# pov-globe2.net
KiCad netlist of a schematic drawn in EAGLE
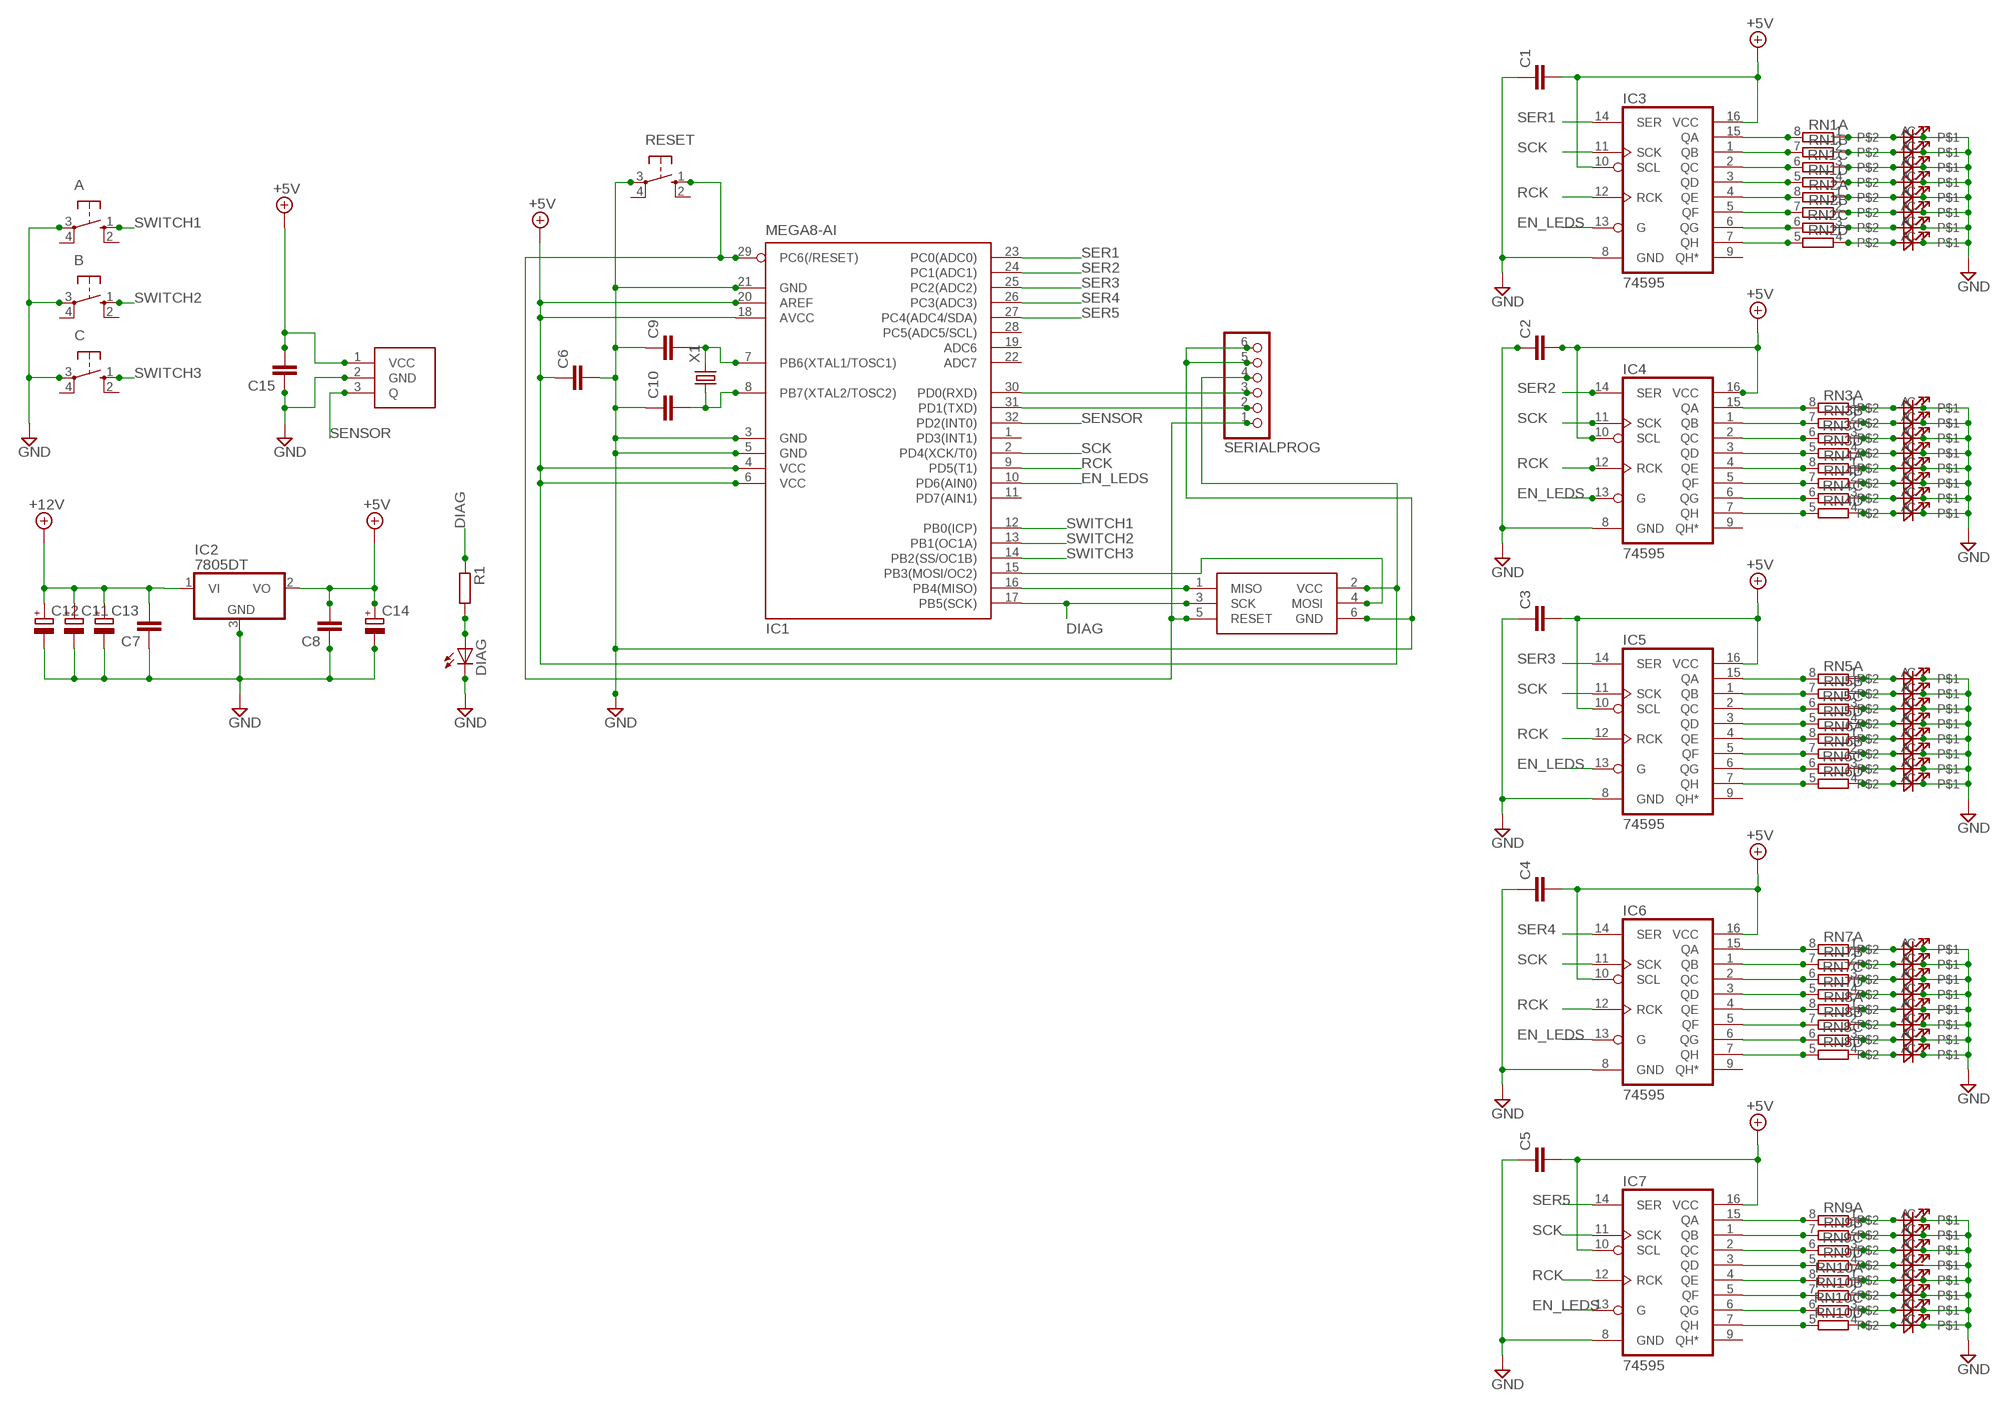
[diagram p0: schematic, sheet 1]

(export (version "E")
  (design (tool "Eeschema 10.0.6"))
  (components
    (comp (ref "0")
      (value "3MMLEDSIDELED1_8MMSIDE")
      (footprint "eagle-import:LED1_8MMSIDE")
      (libsource (lib "eagle-import") (part "3MMLEDSIDELED1_8MMSIDE"))
    )
    (comp (ref "1")
      (value "3MMLEDSIDELED1_8MMSIDE")
      (footprint "eagle-import:LED1_8MMSIDE")
      (libsource (lib "eagle-import") (part "3MMLEDSIDELED1_8MMSIDE"))
    )
    (comp (ref "2")
      (value "3MMLEDSIDELED1_8MMSIDE")
      (footprint "eagle-import:LED1_8MMSIDE")
      (libsource (lib "eagle-import") (part "3MMLEDSIDELED1_8MMSIDE"))
    )
    (comp (ref "3")
      (value "3MMLEDSIDELED1_8MMSIDE")
      (footprint "eagle-import:LED1_8MMSIDE")
      (libsource (lib "eagle-import") (part "3MMLEDSIDELED1_8MMSIDE"))
    )
    (comp (ref "4")
      (value "3MMLEDSIDELED1_8MMSIDE")
      (footprint "eagle-import:LED1_8MMSIDE")
      (libsource (lib "eagle-import") (part "3MMLEDSIDELED1_8MMSIDE"))
    )
    (comp (ref "5")
      (value "3MMLEDSIDELED1_8MMSIDE")
      (footprint "eagle-import:LED1_8MMSIDE")
      (libsource (lib "eagle-import") (part "3MMLEDSIDELED1_8MMSIDE"))
    )
    (comp (ref "6")
      (value "3MMLEDSIDELED1_8MMSIDE")
      (footprint "eagle-import:LED1_8MMSIDE")
      (libsource (lib "eagle-import") (part "3MMLEDSIDELED1_8MMSIDE"))
    )
    (comp (ref "7")
      (value "3MMLEDSIDELED1_8MMSIDE")
      (footprint "eagle-import:LED1_8MMSIDE")
      (libsource (lib "eagle-import") (part "3MMLEDSIDELED1_8MMSIDE"))
    )
    (comp (ref "8")
      (value "3MMLEDSIDELED1_8MMSIDE")
      (footprint "eagle-import:LED1_8MMSIDE")
      (libsource (lib "eagle-import") (part "3MMLEDSIDELED1_8MMSIDE"))
    )
    (comp (ref "9")
      (value "3MMLEDSIDELED1_8MMSIDE")
      (footprint "eagle-import:LED1_8MMSIDE")
      (libsource (lib "eagle-import") (part "3MMLEDSIDELED1_8MMSIDE"))
    )
    (comp (ref "10")
      (value "3MMLEDSIDELED1_8MMSIDE")
      (footprint "eagle-import:LED1_8MMSIDE")
      (libsource (lib "eagle-import") (part "3MMLEDSIDELED1_8MMSIDE"))
    )
    (comp (ref "11")
      (value "3MMLEDSIDELED1_8MMSIDE")
      (footprint "eagle-import:LED1_8MMSIDE")
      (libsource (lib "eagle-import") (part "3MMLEDSIDELED1_8MMSIDE"))
    )
    (comp (ref "12")
      (value "3MMLEDSIDELED1_8MMSIDE")
      (footprint "eagle-import:LED1_8MMSIDE")
      (libsource (lib "eagle-import") (part "3MMLEDSIDELED1_8MMSIDE"))
    )
    (comp (ref "13")
      (value "3MMLEDSIDELED1_8MMSIDE")
      (footprint "eagle-import:LED1_8MMSIDE")
      (libsource (lib "eagle-import") (part "3MMLEDSIDELED1_8MMSIDE"))
    )
    (comp (ref "14")
      (value "3MMLEDSIDELED1_8MMSIDE")
      (footprint "eagle-import:LED1_8MMSIDE")
      (libsource (lib "eagle-import") (part "3MMLEDSIDELED1_8MMSIDE"))
    )
    (comp (ref "15")
      (value "3MMLEDSIDELED1_8MMSIDE")
      (footprint "eagle-import:LED1_8MMSIDE")
      (libsource (lib "eagle-import") (part "3MMLEDSIDELED1_8MMSIDE"))
    )
    (comp (ref "16")
      (value "3MMLEDSIDELED1_8MMSIDE")
      (footprint "eagle-import:LED1_8MMSIDE")
      (libsource (lib "eagle-import") (part "3MMLEDSIDELED1_8MMSIDE"))
    )
    (comp (ref "17")
      (value "3MMLEDSIDELED1_8MMSIDE")
      (footprint "eagle-import:LED1_8MMSIDE")
      (libsource (lib "eagle-import") (part "3MMLEDSIDELED1_8MMSIDE"))
    )
    (comp (ref "18")
      (value "3MMLEDSIDELED1_8MMSIDE")
      (footprint "eagle-import:LED1_8MMSIDE")
      (libsource (lib "eagle-import") (part "3MMLEDSIDELED1_8MMSIDE"))
    )
    (comp (ref "19")
      (value "3MMLEDSIDELED1_8MMSIDE")
      (footprint "eagle-import:LED1_8MMSIDE")
      (libsource (lib "eagle-import") (part "3MMLEDSIDELED1_8MMSIDE"))
    )
    (comp (ref "20")
      (value "3MMLEDSIDELED1_8MMSIDE")
      (footprint "eagle-import:LED1_8MMSIDE")
      (libsource (lib "eagle-import") (part "3MMLEDSIDELED1_8MMSIDE"))
    )
    (comp (ref "21")
      (value "3MMLEDSIDELED1_8MMSIDE")
      (footprint "eagle-import:LED1_8MMSIDE")
      (libsource (lib "eagle-import") (part "3MMLEDSIDELED1_8MMSIDE"))
    )
    (comp (ref "22")
      (value "3MMLEDSIDELED1_8MMSIDE")
      (footprint "eagle-import:LED1_8MMSIDE")
      (libsource (lib "eagle-import") (part "3MMLEDSIDELED1_8MMSIDE"))
    )
    (comp (ref "23")
      (value "3MMLEDSIDELED1_8MMSIDE")
      (footprint "eagle-import:LED1_8MMSIDE")
      (libsource (lib "eagle-import") (part "3MMLEDSIDELED1_8MMSIDE"))
    )
    (comp (ref "24")
      (value "3MMLEDSIDELED1_8MMSIDE")
      (footprint "eagle-import:LED1_8MMSIDE")
      (libsource (lib "eagle-import") (part "3MMLEDSIDELED1_8MMSIDE"))
    )
    (comp (ref "25")
      (value "3MMLEDSIDELED1_8MMSIDE")
      (footprint "eagle-import:LED1_8MMSIDE")
      (libsource (lib "eagle-import") (part "3MMLEDSIDELED1_8MMSIDE"))
    )
    (comp (ref "26")
      (value "3MMLEDSIDELED1_8MMSIDE")
      (footprint "eagle-import:LED1_8MMSIDE")
      (libsource (lib "eagle-import") (part "3MMLEDSIDELED1_8MMSIDE"))
    )
    (comp (ref "27")
      (value "3MMLEDSIDELED1_8MMSIDE")
      (footprint "eagle-import:LED1_8MMSIDE")
      (libsource (lib "eagle-import") (part "3MMLEDSIDELED1_8MMSIDE"))
    )
    (comp (ref "28")
      (value "3MMLEDSIDELED1_8MMSIDE")
      (footprint "eagle-import:LED1_8MMSIDE")
      (libsource (lib "eagle-import") (part "3MMLEDSIDELED1_8MMSIDE"))
    )
    (comp (ref "29")
      (value "3MMLEDSIDELED1_8MMSIDE")
      (footprint "eagle-import:LED1_8MMSIDE")
      (libsource (lib "eagle-import") (part "3MMLEDSIDELED1_8MMSIDE"))
    )
    (comp (ref "30")
      (value "3MMLEDSIDELED1_8MMSIDE")
      (footprint "eagle-import:LED1_8MMSIDE")
      (libsource (lib "eagle-import") (part "3MMLEDSIDELED1_8MMSIDE"))
    )
    (comp (ref "31")
      (value "3MMLEDSIDELED1_8MMSIDE")
      (footprint "eagle-import:LED1_8MMSIDE")
      (libsource (lib "eagle-import") (part "3MMLEDSIDELED1_8MMSIDE"))
    )
    (comp (ref "32")
      (value "3MMLEDSIDELED1_8MMSIDE")
      (footprint "eagle-import:LED1_8MMSIDE")
      (libsource (lib "eagle-import") (part "3MMLEDSIDELED1_8MMSIDE"))
    )
    (comp (ref "33")
      (value "3MMLEDSIDELED1_8MMSIDE")
      (footprint "eagle-import:LED1_8MMSIDE")
      (libsource (lib "eagle-import") (part "3MMLEDSIDELED1_8MMSIDE"))
    )
    (comp (ref "34")
      (value "3MMLEDSIDELED1_8MMSIDE")
      (footprint "eagle-import:LED1_8MMSIDE")
      (libsource (lib "eagle-import") (part "3MMLEDSIDELED1_8MMSIDE"))
    )
    (comp (ref "35")
      (value "3MMLEDSIDELED1_8MMSIDE")
      (footprint "eagle-import:LED1_8MMSIDE")
      (libsource (lib "eagle-import") (part "3MMLEDSIDELED1_8MMSIDE"))
    )
    (comp (ref "36")
      (value "3MMLEDSIDELED1_8MMSIDE")
      (footprint "eagle-import:LED1_8MMSIDE")
      (libsource (lib "eagle-import") (part "3MMLEDSIDELED1_8MMSIDE"))
    )
    (comp (ref "37")
      (value "3MMLEDSIDELED1_8MMSIDE")
      (footprint "eagle-import:LED1_8MMSIDE")
      (libsource (lib "eagle-import") (part "3MMLEDSIDELED1_8MMSIDE"))
    )
    (comp (ref "38")
      (value "3MMLEDSIDELED1_8MMSIDE")
      (footprint "eagle-import:LED1_8MMSIDE")
      (libsource (lib "eagle-import") (part "3MMLEDSIDELED1_8MMSIDE"))
    )
    (comp (ref "39")
      (value "3MMLEDSIDELED1_8MMSIDE")
      (footprint "eagle-import:LED1_8MMSIDE")
      (libsource (lib "eagle-import") (part "3MMLEDSIDELED1_8MMSIDE"))
    )
    (comp (ref "A")
      (value "10-XX")
      (footprint "eagle-import:B3F-10XX")
      (libsource (lib "eagle-import") (part "10-XX"))
    )
    (comp (ref "B")
      (value "10-XX")
      (footprint "eagle-import:B3F-10XX")
      (libsource (lib "eagle-import") (part "10-XX"))
    )
    (comp (ref "C")
      (value "10-XX")
      (footprint "eagle-import:B3F-10XX")
      (libsource (lib "eagle-import") (part "10-XX"))
    )
    (comp (ref "C1")
      (value "C-EUC0805")
      (footprint "eagle-import:C0805")
      (libsource (lib "eagle-import") (part "C-EUC0805"))
    )
    (comp (ref "C2")
      (value "C-EUC0805")
      (footprint "eagle-import:C0805")
      (libsource (lib "eagle-import") (part "C-EUC0805"))
    )
    (comp (ref "C3")
      (value "C-EUC0805")
      (footprint "eagle-import:C0805")
      (libsource (lib "eagle-import") (part "C-EUC0805"))
    )
    (comp (ref "C4")
      (value "C-EUC0805")
      (footprint "eagle-import:C0805")
      (libsource (lib "eagle-import") (part "C-EUC0805"))
    )
    (comp (ref "C5")
      (value "C-EUC0805")
      (footprint "eagle-import:C0805")
      (libsource (lib "eagle-import") (part "C-EUC0805"))
    )
    (comp (ref "C6")
      (value "C-EUC0805")
      (footprint "eagle-import:C0805")
      (libsource (lib "eagle-import") (part "C-EUC0805"))
    )
    (comp (ref "C7")
      (value "C-EUC0805")
      (footprint "eagle-import:C0805")
      (libsource (lib "eagle-import") (part "C-EUC0805"))
    )
    (comp (ref "C8")
      (value "C-EUC0805")
      (footprint "eagle-import:C0805")
      (libsource (lib "eagle-import") (part "C-EUC0805"))
    )
    (comp (ref "C9")
      (value "C-EUC0805")
      (footprint "eagle-import:C0805")
      (libsource (lib "eagle-import") (part "C-EUC0805"))
    )
    (comp (ref "C10")
      (value "C-EUC0805")
      (footprint "eagle-import:C0805")
      (libsource (lib "eagle-import") (part "C-EUC0805"))
    )
    (comp (ref "C11")
      (value "CPOL-EUE2-5")
      (footprint "eagle-import:E2-5")
      (libsource (lib "eagle-import") (part "CPOL-EUE2-5"))
    )
    (comp (ref "C12")
      (value "CPOL-EUE2-5")
      (footprint "eagle-import:E2-5")
      (libsource (lib "eagle-import") (part "CPOL-EUE2-5"))
    )
    (comp (ref "C13")
      (value "CPOL-EUE2-5")
      (footprint "eagle-import:E2-5")
      (libsource (lib "eagle-import") (part "CPOL-EUE2-5"))
    )
    (comp (ref "C14")
      (value "CPOL-EUE2-5")
      (footprint "eagle-import:E2-5")
      (libsource (lib "eagle-import") (part "CPOL-EUE2-5"))
    )
    (comp (ref "C15")
      (value "C-EUC0805")
      (footprint "eagle-import:C0805")
      (libsource (lib "eagle-import") (part "C-EUC0805"))
    )
    (comp (ref "DIAG")
      (value "LEDCHIP-LED0805")
      (footprint "eagle-import:CHIP-LED0805")
      (libsource (lib "eagle-import") (part "LEDCHIP-LED0805"))
    )
    (comp (ref "IC1")
      (value "MEGA8-AI")
      (footprint "eagle-import:TQFP32-08")
      (libsource (lib "eagle-import") (part "MEGA8-AI"))
    )
    (comp (ref "IC2")
      (value "7805DT")
      (footprint "eagle-import:TO252")
      (libsource (lib "eagle-import") (part "78DT05"))
    )
    (comp (ref "IC3")
      (value "74595")
      (footprint "eagle-import:TSSOP16")
      (libsource (lib "eagle-import") (part "74595"))
    )
    (comp (ref "IC4")
      (value "74595")
      (footprint "eagle-import:TSSOP16")
      (libsource (lib "eagle-import") (part "74595"))
    )
    (comp (ref "IC5")
      (value "74595")
      (footprint "eagle-import:TSSOP16")
      (libsource (lib "eagle-import") (part "74595"))
    )
    (comp (ref "IC6")
      (value "74595")
      (footprint "eagle-import:TSSOP16")
      (libsource (lib "eagle-import") (part "74595"))
    )
    (comp (ref "IC7")
      (value "74595")
      (footprint "eagle-import:TSSOP16")
      (libsource (lib "eagle-import") (part "74595"))
    )
    (comp (ref "ICSP")
      (value "TAG_CONN_AVR")
      (footprint "eagle-import:TC2030-MCP-NL")
      (libsource (lib "eagle-import") (part "TAG_CONN_AVR"))
    )
    (comp (ref "R1")
      (value "R-EU_R0805")
      (footprint "eagle-import:R0805")
      (libsource (lib "eagle-import") (part "R-EU_R0805"))
    )
    (comp (ref "RESET")
      (value "10-XX")
      (footprint "eagle-import:B3F-10XX")
      (libsource (lib "eagle-import") (part "10-XX"))
    )
    (comp (ref "RN1")
      (value "4R-N0603-ARC")
      (footprint "eagle-import:0603-ARC")
      (libsource (lib "eagle-import") (part "4R-N0603-ARC"))
    )
    (comp (ref "RN2")
      (value "4R-N0603-ARC")
      (footprint "eagle-import:0603-ARC")
      (libsource (lib "eagle-import") (part "4R-N0603-ARC"))
    )
    (comp (ref "RN3")
      (value "4R-N0603-ARC")
      (footprint "eagle-import:0603-ARC")
      (libsource (lib "eagle-import") (part "4R-N0603-ARC"))
    )
    (comp (ref "RN4")
      (value "4R-N0603-ARC")
      (footprint "eagle-import:0603-ARC")
      (libsource (lib "eagle-import") (part "4R-N0603-ARC"))
    )
    (comp (ref "RN5")
      (value "4R-N0603-ARC")
      (footprint "eagle-import:0603-ARC")
      (libsource (lib "eagle-import") (part "4R-N0603-ARC"))
    )
    (comp (ref "RN6")
      (value "4R-N0603-ARC")
      (footprint "eagle-import:0603-ARC")
      (libsource (lib "eagle-import") (part "4R-N0603-ARC"))
    )
    (comp (ref "RN7")
      (value "4R-N0603-ARC")
      (footprint "eagle-import:0603-ARC")
      (libsource (lib "eagle-import") (part "4R-N0603-ARC"))
    )
    (comp (ref "RN8")
      (value "4R-N0603-ARC")
      (footprint "eagle-import:0603-ARC")
      (libsource (lib "eagle-import") (part "4R-N0603-ARC"))
    )
    (comp (ref "RN9")
      (value "4R-N0603-ARC")
      (footprint "eagle-import:0603-ARC")
      (libsource (lib "eagle-import") (part "4R-N0603-ARC"))
    )
    (comp (ref "RN10")
      (value "4R-N0603-ARC")
      (footprint "eagle-import:0603-ARC")
      (libsource (lib "eagle-import") (part "4R-N0603-ARC"))
    )
    (comp (ref "S1")
      (value "3144HALLSWITCH")
      (footprint "eagle-import:3144HALLSWITCH")
      (libsource (lib "eagle-import") (part "3144HALLSWITCH"))
    )
    (comp (ref "SERIALPROG")
      (value "PINHD-1X6")
      (footprint "eagle-import:1X06")
      (libsource (lib "eagle-import") (part "PINHD-1X6"))
    )
    (comp (ref "X1")
      (value "CRYSTALHC49U-V")
      (footprint "eagle-import:HC49U-V")
      (libsource (lib "eagle-import") (part "CRYSTALHC49U-V"))
    )
  )
  (nets
    (net (code "1") (name "+5V") (class "Default")
      (node (ref "C1") (pin "2") (pinfunction "2_2") (pintype "passive"))
      (node (ref "C14") (pin "+") (pinfunction "+_+") (pintype "passive"))
      (node (ref "C15") (pin "2") (pinfunction "2_2") (pintype "passive"))
      (node (ref "C2") (pin "2") (pinfunction "2_2") (pintype "passive"))
      (node (ref "C3") (pin "2") (pinfunction "2_2") (pintype "passive"))
      (node (ref "C4") (pin "2") (pinfunction "2_2") (pintype "passive"))
      (node (ref "C5") (pin "2") (pinfunction "2_2") (pintype "passive"))
      (node (ref "C6") (pin "1") (pinfunction "1_1") (pintype "passive"))
      (node (ref "C8") (pin "2") (pinfunction "2_2") (pintype "passive"))
      (node (ref "IC1") (pin "18") (pinfunction "AVCC_18") (pintype "power_in"))
      (node (ref "IC1") (pin "20") (pinfunction "AREF_20") (pintype "passive"))
      (node (ref "IC1") (pin "4") (pinfunction "VCC_4") (pintype "power_in"))
      (node (ref "IC1") (pin "6") (pinfunction "VCC_6") (pintype "power_in"))
      (node (ref "IC2") (pin "2") (pinfunction "VO_2") (pintype "passive"))
      (node (ref "IC3") (pin "10") (pinfunction "SCL_10") (pintype "input"))
      (node (ref "IC3") (pin "16") (pinfunction "VCC_16") (pintype "power_in"))
      (node (ref "IC4") (pin "10") (pinfunction "SCL_10") (pintype "input"))
      (node (ref "IC4") (pin "16") (pinfunction "VCC_16") (pintype "power_in"))
      (node (ref "IC5") (pin "10") (pinfunction "SCL_10") (pintype "input"))
      (node (ref "IC5") (pin "16") (pinfunction "VCC_16") (pintype "power_in"))
      (node (ref "IC6") (pin "10") (pinfunction "SCL_10") (pintype "input"))
      (node (ref "IC6") (pin "16") (pinfunction "VCC_16") (pintype "power_in"))
      (node (ref "IC7") (pin "10") (pinfunction "SCL_10") (pintype "input"))
      (node (ref "IC7") (pin "16") (pinfunction "VCC_16") (pintype "power_in"))
      (node (ref "ICSP") (pin "2") (pinfunction "VCC_2") (pintype "power_in"))
      (node (ref "S1") (pin "1") (pinfunction "VCC_1") (pintype "power_in"))
      (node (ref "SERIALPROG") (pin "4") (pinfunction "4_4") (pintype "passive"))
    )
    (net (code "2") (name "+12V") (class "Default")
      (node (ref "C11") (pin "+") (pinfunction "+_+") (pintype "passive"))
      (node (ref "C12") (pin "+") (pinfunction "+_+") (pintype "passive"))
      (node (ref "C13") (pin "+") (pinfunction "+_+") (pintype "passive"))
      (node (ref "C7") (pin "2") (pinfunction "2_2") (pintype "passive"))
      (node (ref "IC2") (pin "1") (pinfunction "VI_1") (pintype "input"))
    )
    (net (code "3") (name "/DIAG") (class "Default")
      (node (ref "IC1") (pin "17") (pinfunction "PB5(SCK)_17") (pintype "bidirectional"))
      (node (ref "ICSP") (pin "3") (pinfunction "SCK_3") (pintype "bidirectional"))
      (node (ref "R1") (pin "1") (pinfunction "1_1") (pintype "passive"))
    )
    (net (code "4") (name "/EN_LEDS") (class "Default")
      (node (ref "IC1") (pin "10") (pinfunction "PD6(AIN0)_10") (pintype "bidirectional"))
      (node (ref "IC3") (pin "13") (pinfunction "G_13") (pintype "input"))
      (node (ref "IC4") (pin "13") (pinfunction "G_13") (pintype "input"))
      (node (ref "IC5") (pin "13") (pinfunction "G_13") (pintype "input"))
      (node (ref "IC6") (pin "13") (pinfunction "G_13") (pintype "input"))
      (node (ref "IC7") (pin "13") (pinfunction "G_13") (pintype "input"))
    )
    (net (code "5") (name "/RCK") (class "Default")
      (node (ref "IC1") (pin "9") (pinfunction "PD5(T1)_9") (pintype "bidirectional"))
      (node (ref "IC3") (pin "12") (pinfunction "RCK_12") (pintype "input"))
      (node (ref "IC4") (pin "12") (pinfunction "RCK_12") (pintype "input"))
      (node (ref "IC5") (pin "12") (pinfunction "RCK_12") (pintype "input"))
      (node (ref "IC6") (pin "12") (pinfunction "RCK_12") (pintype "input"))
      (node (ref "IC7") (pin "12") (pinfunction "RCK_12") (pintype "input"))
    )
    (net (code "6") (name "/SCK") (class "Default")
      (node (ref "IC1") (pin "2") (pinfunction "PD4(XCK/T0)_2") (pintype "bidirectional"))
      (node (ref "IC3") (pin "11") (pinfunction "SCK_11") (pintype "input"))
      (node (ref "IC4") (pin "11") (pinfunction "SCK_11") (pintype "input"))
      (node (ref "IC5") (pin "11") (pinfunction "SCK_11") (pintype "input"))
      (node (ref "IC6") (pin "11") (pinfunction "SCK_11") (pintype "input"))
      (node (ref "IC7") (pin "11") (pinfunction "SCK_11") (pintype "input"))
    )
    (net (code "7") (name "/SENSOR") (class "Default")
      (node (ref "IC1") (pin "32") (pinfunction "PD2(INT0)_32") (pintype "bidirectional"))
      (node (ref "S1") (pin "3") (pinfunction "Q_3") (pintype "open_collector"))
    )
    (net (code "8") (name "/SER1") (class "Default")
      (node (ref "IC1") (pin "23") (pinfunction "PC0(ADC0)_23") (pintype "bidirectional"))
      (node (ref "IC3") (pin "14") (pinfunction "SER_14") (pintype "input"))
    )
    (net (code "9") (name "/SER2") (class "Default")
      (node (ref "IC1") (pin "24") (pinfunction "PC1(ADC1)_24") (pintype "bidirectional"))
      (node (ref "IC4") (pin "14") (pinfunction "SER_14") (pintype "input"))
    )
    (net (code "10") (name "/SER3") (class "Default")
      (node (ref "IC1") (pin "25") (pinfunction "PC2(ADC2)_25") (pintype "bidirectional"))
      (node (ref "IC5") (pin "14") (pinfunction "SER_14") (pintype "input"))
    )
    (net (code "11") (name "/SER4") (class "Default")
      (node (ref "IC1") (pin "26") (pinfunction "PC3(ADC3)_26") (pintype "bidirectional"))
      (node (ref "IC6") (pin "14") (pinfunction "SER_14") (pintype "input"))
    )
    (net (code "12") (name "/SER5") (class "Default")
      (node (ref "IC1") (pin "27") (pinfunction "PC4(ADC4/SDA)_27") (pintype "bidirectional"))
      (node (ref "IC7") (pin "14") (pinfunction "SER_14") (pintype "input"))
    )
    (net (code "13") (name "/SWITCH1") (class "Default")
      (node (ref "A") (pin "1") (pinfunction "S_1") (pintype "passive"))
      (node (ref "IC1") (pin "12") (pinfunction "PB0(ICP)_12") (pintype "bidirectional"))
    )
    (net (code "14") (name "/SWITCH2") (class "Default")
      (node (ref "B") (pin "1") (pinfunction "S_1") (pintype "passive"))
      (node (ref "IC1") (pin "13") (pinfunction "PB1(OC1A)_13") (pintype "bidirectional"))
    )
    (net (code "15") (name "/SWITCH3") (class "Default")
      (node (ref "C") (pin "1") (pinfunction "S_1") (pintype "passive"))
      (node (ref "IC1") (pin "14") (pinfunction "PB2(SS/OC1B)_14") (pintype "bidirectional"))
    )
    (net (code "16") (name "GND") (class "Default")
      (node (ref "0") (pin "C") (pinfunction "P$2_C") (pintype "bidirectional"))
      (node (ref "1") (pin "C") (pinfunction "P$2_C") (pintype "bidirectional"))
      (node (ref "10") (pin "C") (pinfunction "P$2_C") (pintype "bidirectional"))
      (node (ref "11") (pin "C") (pinfunction "P$2_C") (pintype "bidirectional"))
      (node (ref "12") (pin "C") (pinfunction "P$2_C") (pintype "bidirectional"))
      (node (ref "13") (pin "C") (pinfunction "P$2_C") (pintype "bidirectional"))
      (node (ref "14") (pin "C") (pinfunction "P$2_C") (pintype "bidirectional"))
      (node (ref "15") (pin "C") (pinfunction "P$2_C") (pintype "bidirectional"))
      (node (ref "16") (pin "C") (pinfunction "P$2_C") (pintype "bidirectional"))
      (node (ref "17") (pin "C") (pinfunction "P$2_C") (pintype "bidirectional"))
      (node (ref "18") (pin "C") (pinfunction "P$2_C") (pintype "bidirectional"))
      (node (ref "19") (pin "C") (pinfunction "P$2_C") (pintype "bidirectional"))
      (node (ref "2") (pin "C") (pinfunction "P$2_C") (pintype "bidirectional"))
      (node (ref "20") (pin "C") (pinfunction "P$2_C") (pintype "bidirectional"))
      (node (ref "21") (pin "C") (pinfunction "P$2_C") (pintype "bidirectional"))
      (node (ref "22") (pin "C") (pinfunction "P$2_C") (pintype "bidirectional"))
      (node (ref "23") (pin "C") (pinfunction "P$2_C") (pintype "bidirectional"))
      (node (ref "24") (pin "C") (pinfunction "P$2_C") (pintype "bidirectional"))
      (node (ref "25") (pin "C") (pinfunction "P$2_C") (pintype "bidirectional"))
      (node (ref "26") (pin "C") (pinfunction "P$2_C") (pintype "bidirectional"))
      (node (ref "27") (pin "C") (pinfunction "P$2_C") (pintype "bidirectional"))
      (node (ref "28") (pin "C") (pinfunction "P$2_C") (pintype "bidirectional"))
      (node (ref "29") (pin "C") (pinfunction "P$2_C") (pintype "bidirectional"))
      (node (ref "3") (pin "C") (pinfunction "P$2_C") (pintype "bidirectional"))
      (node (ref "30") (pin "C") (pinfunction "P$2_C") (pintype "bidirectional"))
      (node (ref "31") (pin "C") (pinfunction "P$2_C") (pintype "bidirectional"))
      (node (ref "32") (pin "C") (pinfunction "P$2_C") (pintype "bidirectional"))
      (node (ref "33") (pin "C") (pinfunction "P$2_C") (pintype "bidirectional"))
      (node (ref "34") (pin "C") (pinfunction "P$2_C") (pintype "bidirectional"))
      (node (ref "35") (pin "C") (pinfunction "P$2_C") (pintype "bidirectional"))
      (node (ref "36") (pin "C") (pinfunction "P$2_C") (pintype "bidirectional"))
      (node (ref "37") (pin "C") (pinfunction "P$2_C") (pintype "bidirectional"))
      (node (ref "38") (pin "C") (pinfunction "P$2_C") (pintype "bidirectional"))
      (node (ref "39") (pin "C") (pinfunction "P$2_C") (pintype "bidirectional"))
      (node (ref "4") (pin "C") (pinfunction "P$2_C") (pintype "bidirectional"))
      (node (ref "5") (pin "C") (pinfunction "P$2_C") (pintype "bidirectional"))
      (node (ref "6") (pin "C") (pinfunction "P$2_C") (pintype "bidirectional"))
      (node (ref "7") (pin "C") (pinfunction "P$2_C") (pintype "bidirectional"))
      (node (ref "8") (pin "C") (pinfunction "P$2_C") (pintype "bidirectional"))
      (node (ref "9") (pin "C") (pinfunction "P$2_C") (pintype "bidirectional"))
      (node (ref "A") (pin "3") (pinfunction "P_3") (pintype "passive"))
      (node (ref "B") (pin "3") (pinfunction "P_3") (pintype "passive"))
      (node (ref "C") (pin "3") (pinfunction "P_3") (pintype "passive"))
      (node (ref "C1") (pin "1") (pinfunction "1_1") (pintype "passive"))
      (node (ref "C10") (pin "1") (pinfunction "1_1") (pintype "passive"))
      (node (ref "C11") (pin "-") (pinfunction "-_-") (pintype "passive"))
      (node (ref "C12") (pin "-") (pinfunction "-_-") (pintype "passive"))
      (node (ref "C13") (pin "-") (pinfunction "-_-") (pintype "passive"))
      (node (ref "C14") (pin "-") (pinfunction "-_-") (pintype "passive"))
      (node (ref "C15") (pin "1") (pinfunction "1_1") (pintype "passive"))
      (node (ref "C2") (pin "1") (pinfunction "1_1") (pintype "passive"))
      (node (ref "C3") (pin "1") (pinfunction "1_1") (pintype "passive"))
      (node (ref "C4") (pin "1") (pinfunction "1_1") (pintype "passive"))
      (node (ref "C5") (pin "1") (pinfunction "1_1") (pintype "passive"))
      (node (ref "C6") (pin "2") (pinfunction "2_2") (pintype "passive"))
      (node (ref "C7") (pin "1") (pinfunction "1_1") (pintype "passive"))
      (node (ref "C8") (pin "1") (pinfunction "1_1") (pintype "passive"))
      (node (ref "C9") (pin "1") (pinfunction "1_1") (pintype "passive"))
      (node (ref "DIAG") (pin "C") (pinfunction "C_C") (pintype "passive"))
      (node (ref "IC1") (pin "21") (pinfunction "GND_21") (pintype "power_in"))
      (node (ref "IC1") (pin "3") (pinfunction "GND_3") (pintype "power_in"))
      (node (ref "IC1") (pin "5") (pinfunction "GND_5") (pintype "power_in"))
      (node (ref "IC2") (pin "3") (pinfunction "GND_3") (pintype "passive"))
      (node (ref "IC3") (pin "8") (pinfunction "GND_8") (pintype "power_in"))
      (node (ref "IC4") (pin "8") (pinfunction "GND_8") (pintype "power_in"))
      (node (ref "IC5") (pin "8") (pinfunction "GND_8") (pintype "power_in"))
      (node (ref "IC6") (pin "8") (pinfunction "GND_8") (pintype "power_in"))
      (node (ref "IC7") (pin "8") (pinfunction "GND_8") (pintype "power_in"))
      (node (ref "ICSP") (pin "6") (pinfunction "GND_6") (pintype "power_in"))
      (node (ref "RESET") (pin "3") (pinfunction "P_3") (pintype "passive"))
      (node (ref "S1") (pin "2") (pinfunction "GND_2") (pintype "power_in"))
      (node (ref "SERIALPROG") (pin "5") (pinfunction "5_5") (pintype "passive"))
      (node (ref "SERIALPROG") (pin "6") (pinfunction "6_6") (pintype "passive"))
    )
    (net (code "17") (name "Net-(0-P$1)") (class "Default")
      (node (ref "0") (pin "A") (pinfunction "P$1_A") (pintype "bidirectional"))
      (node (ref "RN1") (pin "1") (pinfunction "1_1") (pintype "passive"))
    )
    (net (code "18") (name "Net-(1-P$1)") (class "Default")
      (node (ref "1") (pin "A") (pinfunction "P$1_A") (pintype "bidirectional"))
      (node (ref "RN1") (pin "2") (pinfunction "1_2") (pintype "passive"))
    )
    (net (code "19") (name "Net-(2-P$1)") (class "Default")
      (node (ref "2") (pin "A") (pinfunction "P$1_A") (pintype "bidirectional"))
      (node (ref "RN1") (pin "3") (pinfunction "1_3") (pintype "passive"))
    )
    (net (code "20") (name "Net-(3-P$1)") (class "Default")
      (node (ref "3") (pin "A") (pinfunction "P$1_A") (pintype "bidirectional"))
      (node (ref "RN1") (pin "4") (pinfunction "1_4") (pintype "passive"))
    )
    (net (code "21") (name "Net-(4-P$1)") (class "Default")
      (node (ref "4") (pin "A") (pinfunction "P$1_A") (pintype "bidirectional"))
      (node (ref "RN2") (pin "1") (pinfunction "1_1") (pintype "passive"))
    )
    (net (code "22") (name "Net-(5-P$1)") (class "Default")
      (node (ref "5") (pin "A") (pinfunction "P$1_A") (pintype "bidirectional"))
      (node (ref "RN2") (pin "2") (pinfunction "1_2") (pintype "passive"))
    )
    (net (code "23") (name "Net-(6-P$1)") (class "Default")
      (node (ref "6") (pin "A") (pinfunction "P$1_A") (pintype "bidirectional"))
      (node (ref "RN2") (pin "3") (pinfunction "1_3") (pintype "passive"))
    )
    (net (code "24") (name "Net-(7-P$1)") (class "Default")
      (node (ref "7") (pin "A") (pinfunction "P$1_A") (pintype "bidirectional"))
      (node (ref "RN2") (pin "4") (pinfunction "1_4") (pintype "passive"))
    )
    (net (code "25") (name "Net-(8-P$1)") (class "Default")
      (node (ref "8") (pin "A") (pinfunction "P$1_A") (pintype "bidirectional"))
      (node (ref "RN3") (pin "1") (pinfunction "1_1") (pintype "passive"))
    )
    (net (code "26") (name "Net-(9-P$1)") (class "Default")
      (node (ref "9") (pin "A") (pinfunction "P$1_A") (pintype "bidirectional"))
      (node (ref "RN3") (pin "2") (pinfunction "1_2") (pintype "passive"))
    )
    (net (code "27") (name "Net-(10-P$1)") (class "Default")
      (node (ref "10") (pin "A") (pinfunction "P$1_A") (pintype "bidirectional"))
      (node (ref "RN3") (pin "3") (pinfunction "1_3") (pintype "passive"))
    )
    (net (code "28") (name "Net-(11-P$1)") (class "Default")
      (node (ref "11") (pin "A") (pinfunction "P$1_A") (pintype "bidirectional"))
      (node (ref "RN3") (pin "4") (pinfunction "1_4") (pintype "passive"))
    )
    (net (code "29") (name "Net-(12-P$1)") (class "Default")
      (node (ref "12") (pin "A") (pinfunction "P$1_A") (pintype "bidirectional"))
      (node (ref "RN4") (pin "1") (pinfunction "1_1") (pintype "passive"))
    )
    (net (code "30") (name "Net-(13-P$1)") (class "Default")
      (node (ref "13") (pin "A") (pinfunction "P$1_A") (pintype "bidirectional"))
      (node (ref "RN4") (pin "2") (pinfunction "1_2") (pintype "passive"))
    )
    (net (code "31") (name "Net-(14-P$1)") (class "Default")
      (node (ref "14") (pin "A") (pinfunction "P$1_A") (pintype "bidirectional"))
      (node (ref "RN4") (pin "3") (pinfunction "1_3") (pintype "passive"))
    )
    (net (code "32") (name "Net-(15-P$1)") (class "Default")
      (node (ref "15") (pin "A") (pinfunction "P$1_A") (pintype "bidirectional"))
      (node (ref "RN4") (pin "4") (pinfunction "1_4") (pintype "passive"))
    )
    (net (code "33") (name "Net-(16-P$1)") (class "Default")
      (node (ref "16") (pin "A") (pinfunction "P$1_A") (pintype "bidirectional"))
      (node (ref "RN5") (pin "1") (pinfunction "1_1") (pintype "passive"))
    )
    (net (code "34") (name "Net-(17-P$1)") (class "Default")
      (node (ref "17") (pin "A") (pinfunction "P$1_A") (pintype "bidirectional"))
      (node (ref "RN5") (pin "2") (pinfunction "1_2") (pintype "passive"))
    )
    (net (code "35") (name "Net-(18-P$1)") (class "Default")
      (node (ref "18") (pin "A") (pinfunction "P$1_A") (pintype "bidirectional"))
      (node (ref "RN5") (pin "3") (pinfunction "1_3") (pintype "passive"))
    )
    (net (code "36") (name "Net-(19-P$1)") (class "Default")
      (node (ref "19") (pin "A") (pinfunction "P$1_A") (pintype "bidirectional"))
      (node (ref "RN5") (pin "4") (pinfunction "1_4") (pintype "passive"))
    )
    (net (code "37") (name "Net-(20-P$1)") (class "Default")
      (node (ref "20") (pin "A") (pinfunction "P$1_A") (pintype "bidirectional"))
      (node (ref "RN6") (pin "1") (pinfunction "1_1") (pintype "passive"))
    )
    (net (code "38") (name "Net-(21-P$1)") (class "Default")
      (node (ref "21") (pin "A") (pinfunction "P$1_A") (pintype "bidirectional"))
      (node (ref "RN6") (pin "2") (pinfunction "1_2") (pintype "passive"))
    )
    (net (code "39") (name "Net-(22-P$1)") (class "Default")
      (node (ref "22") (pin "A") (pinfunction "P$1_A") (pintype "bidirectional"))
      (node (ref "RN6") (pin "3") (pinfunction "1_3") (pintype "passive"))
    )
    (net (code "40") (name "Net-(23-P$1)") (class "Default")
      (node (ref "23") (pin "A") (pinfunction "P$1_A") (pintype "bidirectional"))
      (node (ref "RN6") (pin "4") (pinfunction "1_4") (pintype "passive"))
    )
    (net (code "41") (name "Net-(24-P$1)") (class "Default")
      (node (ref "24") (pin "A") (pinfunction "P$1_A") (pintype "bidirectional"))
      (node (ref "RN7") (pin "1") (pinfunction "1_1") (pintype "passive"))
    )
    (net (code "42") (name "Net-(25-P$1)") (class "Default")
      (node (ref "25") (pin "A") (pinfunction "P$1_A") (pintype "bidirectional"))
      (node (ref "RN7") (pin "2") (pinfunction "1_2") (pintype "passive"))
    )
    (net (code "43") (name "Net-(26-P$1)") (class "Default")
      (node (ref "26") (pin "A") (pinfunction "P$1_A") (pintype "bidirectional"))
      (node (ref "RN7") (pin "3") (pinfunction "1_3") (pintype "passive"))
    )
    (net (code "44") (name "Net-(27-P$1)") (class "Default")
      (node (ref "27") (pin "A") (pinfunction "P$1_A") (pintype "bidirectional"))
      (node (ref "RN7") (pin "4") (pinfunction "1_4") (pintype "passive"))
    )
    (net (code "45") (name "Net-(28-P$1)") (class "Default")
      (node (ref "28") (pin "A") (pinfunction "P$1_A") (pintype "bidirectional"))
      (node (ref "RN8") (pin "1") (pinfunction "1_1") (pintype "passive"))
    )
    (net (code "46") (name "Net-(29-P$1)") (class "Default")
      (node (ref "29") (pin "A") (pinfunction "P$1_A") (pintype "bidirectional"))
      (node (ref "RN8") (pin "2") (pinfunction "1_2") (pintype "passive"))
    )
    (net (code "47") (name "Net-(30-P$1)") (class "Default")
      (node (ref "30") (pin "A") (pinfunction "P$1_A") (pintype "bidirectional"))
      (node (ref "RN8") (pin "3") (pinfunction "1_3") (pintype "passive"))
    )
    (net (code "48") (name "Net-(31-P$1)") (class "Default")
      (node (ref "31") (pin "A") (pinfunction "P$1_A") (pintype "bidirectional"))
      (node (ref "RN8") (pin "4") (pinfunction "1_4") (pintype "passive"))
    )
    (net (code "49") (name "Net-(32-P$1)") (class "Default")
      (node (ref "32") (pin "A") (pinfunction "P$1_A") (pintype "bidirectional"))
      (node (ref "RN9") (pin "1") (pinfunction "1_1") (pintype "passive"))
    )
    (net (code "50") (name "Net-(33-P$1)") (class "Default")
      (node (ref "33") (pin "A") (pinfunction "P$1_A") (pintype "bidirectional"))
      (node (ref "RN9") (pin "2") (pinfunction "1_2") (pintype "passive"))
    )
    (net (code "51") (name "Net-(34-P$1)") (class "Default")
      (node (ref "34") (pin "A") (pinfunction "P$1_A") (pintype "bidirectional"))
      (node (ref "RN9") (pin "3") (pinfunction "1_3") (pintype "passive"))
    )
    (net (code "52") (name "Net-(35-P$1)") (class "Default")
      (node (ref "35") (pin "A") (pinfunction "P$1_A") (pintype "bidirectional"))
      (node (ref "RN9") (pin "4") (pinfunction "1_4") (pintype "passive"))
    )
    (net (code "53") (name "Net-(36-P$1)") (class "Default")
      (node (ref "36") (pin "A") (pinfunction "P$1_A") (pintype "bidirectional"))
      (node (ref "RN10") (pin "1") (pinfunction "1_1") (pintype "passive"))
    )
    (net (code "54") (name "Net-(37-P$1)") (class "Default")
      (node (ref "37") (pin "A") (pinfunction "P$1_A") (pintype "bidirectional"))
      (node (ref "RN10") (pin "2") (pinfunction "1_2") (pintype "passive"))
    )
    (net (code "55") (name "Net-(38-P$1)") (class "Default")
      (node (ref "38") (pin "A") (pinfunction "P$1_A") (pintype "bidirectional"))
      (node (ref "RN10") (pin "3") (pinfunction "1_3") (pintype "passive"))
    )
    (net (code "56") (name "Net-(39-P$1)") (class "Default")
      (node (ref "39") (pin "A") (pinfunction "P$1_A") (pintype "bidirectional"))
      (node (ref "RN10") (pin "4") (pinfunction "1_4") (pintype "passive"))
    )
    (net (code "57") (name "Net-(DIAG-PadA)") (class "Default")
      (node (ref "DIAG") (pin "A") (pinfunction "A_A") (pintype "passive"))
      (node (ref "R1") (pin "2") (pinfunction "2_2") (pintype "passive"))
    )
    (net (code "58") (name "Net-(IC1-PB3(MOSI{slash}OC2))") (class "Default")
      (node (ref "IC1") (pin "15") (pinfunction "PB3(MOSI/OC2)_15") (pintype "bidirectional"))
      (node (ref "ICSP") (pin "4") (pinfunction "MOSI_4") (pintype "bidirectional"))
    )
    (net (code "59") (name "Net-(IC1-PB4(MISO))") (class "Default")
      (node (ref "IC1") (pin "16") (pinfunction "PB4(MISO)_16") (pintype "bidirectional"))
      (node (ref "ICSP") (pin "1") (pinfunction "MISO_1") (pintype "bidirectional"))
    )
    (net (code "60") (name "Net-(IC1-PB6(XTAL1{slash}TOSC1))") (class "Default")
      (node (ref "C9") (pin "2") (pinfunction "2_2") (pintype "passive"))
      (node (ref "IC1") (pin "7") (pinfunction "PB6(XTAL1/TOSC1)_7") (pintype "bidirectional"))
      (node (ref "X1") (pin "2") (pinfunction "2_2") (pintype "passive"))
    )
    (net (code "61") (name "Net-(IC1-PB7(XTAL2{slash}TOSC2))") (class "Default")
      (node (ref "C10") (pin "2") (pinfunction "2_2") (pintype "passive"))
      (node (ref "IC1") (pin "8") (pinfunction "PB7(XTAL2/TOSC2)_8") (pintype "bidirectional"))
      (node (ref "X1") (pin "1") (pinfunction "1_1") (pintype "passive"))
    )
    (net (code "62") (name "Net-(IC1-PC6({slash}RESET))") (class "Default")
      (node (ref "IC1") (pin "29") (pinfunction "PC6(/RESET)_29") (pintype "bidirectional"))
      (node (ref "ICSP") (pin "5") (pinfunction "RESET_5") (pintype "bidirectional"))
      (node (ref "RESET") (pin "1") (pinfunction "S_1") (pintype "passive"))
      (node (ref "SERIALPROG") (pin "1") (pinfunction "1_1") (pintype "passive"))
    )
    (net (code "63") (name "Net-(IC1-PD0(RXD))") (class "Default")
      (node (ref "IC1") (pin "30") (pinfunction "PD0(RXD)_30") (pintype "bidirectional"))
      (node (ref "SERIALPROG") (pin "3") (pinfunction "3_3") (pintype "passive"))
    )
    (net (code "64") (name "Net-(IC1-PD1(TXD))") (class "Default")
      (node (ref "IC1") (pin "31") (pinfunction "PD1(TXD)_31") (pintype "bidirectional"))
      (node (ref "SERIALPROG") (pin "2") (pinfunction "2_2") (pintype "passive"))
    )
    (net (code "65") (name "Net-(IC3-QA)") (class "Default")
      (node (ref "IC3") (pin "15") (pinfunction "QA_15") (pintype "tri_state"))
      (node (ref "RN1") (pin "8") (pinfunction "2_8") (pintype "passive"))
    )
    (net (code "66") (name "Net-(IC3-QB)") (class "Default")
      (node (ref "IC3") (pin "1") (pinfunction "QB_1") (pintype "tri_state"))
      (node (ref "RN1") (pin "7") (pinfunction "2_7") (pintype "passive"))
    )
    (net (code "67") (name "Net-(IC3-QC)") (class "Default")
      (node (ref "IC3") (pin "2") (pinfunction "QC_2") (pintype "tri_state"))
      (node (ref "RN1") (pin "6") (pinfunction "2_6") (pintype "passive"))
    )
    (net (code "68") (name "Net-(IC3-QD)") (class "Default")
      (node (ref "IC3") (pin "3") (pinfunction "QD_3") (pintype "tri_state"))
      (node (ref "RN1") (pin "5") (pinfunction "2_5") (pintype "passive"))
    )
    (net (code "69") (name "Net-(IC3-QE)") (class "Default")
      (node (ref "IC3") (pin "4") (pinfunction "QE_4") (pintype "tri_state"))
      (node (ref "RN2") (pin "8") (pinfunction "2_8") (pintype "passive"))
    )
    (net (code "70") (name "Net-(IC3-QF)") (class "Default")
      (node (ref "IC3") (pin "5") (pinfunction "QF_5") (pintype "tri_state"))
      (node (ref "RN2") (pin "7") (pinfunction "2_7") (pintype "passive"))
    )
    (net (code "71") (name "Net-(IC3-QG)") (class "Default")
      (node (ref "IC3") (pin "6") (pinfunction "QG_6") (pintype "tri_state"))
      (node (ref "RN2") (pin "6") (pinfunction "2_6") (pintype "passive"))
    )
    (net (code "72") (name "Net-(IC3-QH)") (class "Default")
      (node (ref "IC3") (pin "7") (pinfunction "QH_7") (pintype "tri_state"))
      (node (ref "RN2") (pin "5") (pinfunction "2_5") (pintype "passive"))
    )
    (net (code "73") (name "Net-(IC4-QA)") (class "Default")
      (node (ref "IC4") (pin "15") (pinfunction "QA_15") (pintype "tri_state"))
      (node (ref "RN3") (pin "8") (pinfunction "2_8") (pintype "passive"))
    )
    (net (code "74") (name "Net-(IC4-QB)") (class "Default")
      (node (ref "IC4") (pin "1") (pinfunction "QB_1") (pintype "tri_state"))
      (node (ref "RN3") (pin "7") (pinfunction "2_7") (pintype "passive"))
    )
    (net (code "75") (name "Net-(IC4-QC)") (class "Default")
      (node (ref "IC4") (pin "2") (pinfunction "QC_2") (pintype "tri_state"))
      (node (ref "RN3") (pin "6") (pinfunction "2_6") (pintype "passive"))
    )
    (net (code "76") (name "Net-(IC4-QD)") (class "Default")
      (node (ref "IC4") (pin "3") (pinfunction "QD_3") (pintype "tri_state"))
      (node (ref "RN3") (pin "5") (pinfunction "2_5") (pintype "passive"))
    )
    (net (code "77") (name "Net-(IC4-QE)") (class "Default")
      (node (ref "IC4") (pin "4") (pinfunction "QE_4") (pintype "tri_state"))
      (node (ref "RN4") (pin "8") (pinfunction "2_8") (pintype "passive"))
    )
    (net (code "78") (name "Net-(IC4-QF)") (class "Default")
      (node (ref "IC4") (pin "5") (pinfunction "QF_5") (pintype "tri_state"))
      (node (ref "RN4") (pin "7") (pinfunction "2_7") (pintype "passive"))
    )
    (net (code "79") (name "Net-(IC4-QG)") (class "Default")
      (node (ref "IC4") (pin "6") (pinfunction "QG_6") (pintype "tri_state"))
      (node (ref "RN4") (pin "6") (pinfunction "2_6") (pintype "passive"))
    )
    (net (code "80") (name "Net-(IC4-QH)") (class "Default")
      (node (ref "IC4") (pin "7") (pinfunction "QH_7") (pintype "tri_state"))
      (node (ref "RN4") (pin "5") (pinfunction "2_5") (pintype "passive"))
    )
    (net (code "81") (name "Net-(IC5-QA)") (class "Default")
      (node (ref "IC5") (pin "15") (pinfunction "QA_15") (pintype "tri_state"))
      (node (ref "RN5") (pin "8") (pinfunction "2_8") (pintype "passive"))
    )
    (net (code "82") (name "Net-(IC5-QB)") (class "Default")
      (node (ref "IC5") (pin "1") (pinfunction "QB_1") (pintype "tri_state"))
      (node (ref "RN5") (pin "7") (pinfunction "2_7") (pintype "passive"))
    )
    (net (code "83") (name "Net-(IC5-QC)") (class "Default")
      (node (ref "IC5") (pin "2") (pinfunction "QC_2") (pintype "tri_state"))
      (node (ref "RN5") (pin "6") (pinfunction "2_6") (pintype "passive"))
    )
    (net (code "84") (name "Net-(IC5-QD)") (class "Default")
      (node (ref "IC5") (pin "3") (pinfunction "QD_3") (pintype "tri_state"))
      (node (ref "RN5") (pin "5") (pinfunction "2_5") (pintype "passive"))
    )
    (net (code "85") (name "Net-(IC5-QE)") (class "Default")
      (node (ref "IC5") (pin "4") (pinfunction "QE_4") (pintype "tri_state"))
      (node (ref "RN6") (pin "8") (pinfunction "2_8") (pintype "passive"))
    )
    (net (code "86") (name "Net-(IC5-QF)") (class "Default")
      (node (ref "IC5") (pin "5") (pinfunction "QF_5") (pintype "tri_state"))
      (node (ref "RN6") (pin "7") (pinfunction "2_7") (pintype "passive"))
    )
    (net (code "87") (name "Net-(IC5-QG)") (class "Default")
      (node (ref "IC5") (pin "6") (pinfunction "QG_6") (pintype "tri_state"))
      (node (ref "RN6") (pin "6") (pinfunction "2_6") (pintype "passive"))
    )
    (net (code "88") (name "Net-(IC5-QH)") (class "Default")
      (node (ref "IC5") (pin "7") (pinfunction "QH_7") (pintype "tri_state"))
      (node (ref "RN6") (pin "5") (pinfunction "2_5") (pintype "passive"))
    )
    (net (code "89") (name "Net-(IC6-QA)") (class "Default")
      (node (ref "IC6") (pin "15") (pinfunction "QA_15") (pintype "tri_state"))
      (node (ref "RN7") (pin "8") (pinfunction "2_8") (pintype "passive"))
    )
    (net (code "90") (name "Net-(IC6-QB)") (class "Default")
      (node (ref "IC6") (pin "1") (pinfunction "QB_1") (pintype "tri_state"))
      (node (ref "RN7") (pin "7") (pinfunction "2_7") (pintype "passive"))
    )
    (net (code "91") (name "Net-(IC6-QC)") (class "Default")
      (node (ref "IC6") (pin "2") (pinfunction "QC_2") (pintype "tri_state"))
      (node (ref "RN7") (pin "6") (pinfunction "2_6") (pintype "passive"))
    )
    (net (code "92") (name "Net-(IC6-QD)") (class "Default")
      (node (ref "IC6") (pin "3") (pinfunction "QD_3") (pintype "tri_state"))
      (node (ref "RN7") (pin "5") (pinfunction "2_5") (pintype "passive"))
    )
    (net (code "93") (name "Net-(IC6-QE)") (class "Default")
      (node (ref "IC6") (pin "4") (pinfunction "QE_4") (pintype "tri_state"))
      (node (ref "RN8") (pin "8") (pinfunction "2_8") (pintype "passive"))
    )
    (net (code "94") (name "Net-(IC6-QF)") (class "Default")
      (node (ref "IC6") (pin "5") (pinfunction "QF_5") (pintype "tri_state"))
      (node (ref "RN8") (pin "7") (pinfunction "2_7") (pintype "passive"))
    )
    (net (code "95") (name "Net-(IC6-QG)") (class "Default")
      (node (ref "IC6") (pin "6") (pinfunction "QG_6") (pintype "tri_state"))
      (node (ref "RN8") (pin "6") (pinfunction "2_6") (pintype "passive"))
    )
    (net (code "96") (name "Net-(IC6-QH)") (class "Default")
      (node (ref "IC6") (pin "7") (pinfunction "QH_7") (pintype "tri_state"))
      (node (ref "RN8") (pin "5") (pinfunction "2_5") (pintype "passive"))
    )
    (net (code "97") (name "Net-(IC7-QA)") (class "Default")
      (node (ref "IC7") (pin "15") (pinfunction "QA_15") (pintype "tri_state"))
      (node (ref "RN9") (pin "8") (pinfunction "2_8") (pintype "passive"))
    )
    (net (code "98") (name "Net-(IC7-QB)") (class "Default")
      (node (ref "IC7") (pin "1") (pinfunction "QB_1") (pintype "tri_state"))
      (node (ref "RN9") (pin "7") (pinfunction "2_7") (pintype "passive"))
    )
    (net (code "99") (name "Net-(IC7-QC)") (class "Default")
      (node (ref "IC7") (pin "2") (pinfunction "QC_2") (pintype "tri_state"))
      (node (ref "RN9") (pin "6") (pinfunction "2_6") (pintype "passive"))
    )
    (net (code "100") (name "Net-(IC7-QD)") (class "Default")
      (node (ref "IC7") (pin "3") (pinfunction "QD_3") (pintype "tri_state"))
      (node (ref "RN9") (pin "5") (pinfunction "2_5") (pintype "passive"))
    )
    (net (code "101") (name "Net-(IC7-QE)") (class "Default")
      (node (ref "IC7") (pin "4") (pinfunction "QE_4") (pintype "tri_state"))
      (node (ref "RN10") (pin "8") (pinfunction "2_8") (pintype "passive"))
    )
    (net (code "102") (name "Net-(IC7-QF)") (class "Default")
      (node (ref "IC7") (pin "5") (pinfunction "QF_5") (pintype "tri_state"))
      (node (ref "RN10") (pin "7") (pinfunction "2_7") (pintype "passive"))
    )
    (net (code "103") (name "Net-(IC7-QG)") (class "Default")
      (node (ref "IC7") (pin "6") (pinfunction "QG_6") (pintype "tri_state"))
      (node (ref "RN10") (pin "6") (pinfunction "2_6") (pintype "passive"))
    )
    (net (code "104") (name "Net-(IC7-QH)") (class "Default")
      (node (ref "IC7") (pin "7") (pinfunction "QH_7") (pintype "tri_state"))
      (node (ref "RN10") (pin "5") (pinfunction "2_5") (pintype "passive"))
    )
    (net (code "105") (name "unconnected-(A-P1-Pad4)") (class "Default")
      (node (ref "A") (pin "4") (pinfunction "P1_4") (pintype "passive"))
    )
    (net (code "106") (name "unconnected-(A-S1-Pad2)") (class "Default")
      (node (ref "A") (pin "2") (pinfunction "S1_2") (pintype "passive"))
    )
    (net (code "107") (name "unconnected-(B-P1-Pad4)") (class "Default")
      (node (ref "B") (pin "4") (pinfunction "P1_4") (pintype "passive"))
    )
    (net (code "108") (name "unconnected-(B-S1-Pad2)") (class "Default")
      (node (ref "B") (pin "2") (pinfunction "S1_2") (pintype "passive"))
    )
    (net (code "109") (name "unconnected-(C-P1-Pad4)") (class "Default")
      (node (ref "C") (pin "4") (pinfunction "P1_4") (pintype "passive"))
    )
    (net (code "110") (name "unconnected-(C-S1-Pad2)") (class "Default")
      (node (ref "C") (pin "2") (pinfunction "S1_2") (pintype "passive"))
    )
    (net (code "111") (name "unconnected-(IC1-ADC6-Pad19)") (class "Default")
      (node (ref "IC1") (pin "19") (pinfunction "ADC6_19") (pintype "bidirectional"))
    )
    (net (code "112") (name "unconnected-(IC1-ADC7-Pad22)") (class "Default")
      (node (ref "IC1") (pin "22") (pinfunction "ADC7_22") (pintype "bidirectional"))
    )
    (net (code "113") (name "unconnected-(IC1-PC5(ADC5{slash}SCL)-Pad28)") (class "Default")
      (node (ref "IC1") (pin "28") (pinfunction "PC5(ADC5/SCL)_28") (pintype "bidirectional"))
    )
    (net (code "114") (name "unconnected-(IC1-PD3(INT1)-Pad1)") (class "Default")
      (node (ref "IC1") (pin "1") (pinfunction "PD3(INT1)_1") (pintype "bidirectional"))
    )
    (net (code "115") (name "unconnected-(IC1-PD7(AIN1)-Pad11)") (class "Default")
      (node (ref "IC1") (pin "11") (pinfunction "PD7(AIN1)_11") (pintype "bidirectional"))
    )
    (net (code "116") (name "unconnected-(IC3-QH*-Pad9)") (class "Default")
      (node (ref "IC3") (pin "9") (pinfunction "QH*_9") (pintype "tri_state"))
    )
    (net (code "117") (name "unconnected-(IC4-QH*-Pad9)") (class "Default")
      (node (ref "IC4") (pin "9") (pinfunction "QH*_9") (pintype "tri_state"))
    )
    (net (code "118") (name "unconnected-(IC5-QH*-Pad9)") (class "Default")
      (node (ref "IC5") (pin "9") (pinfunction "QH*_9") (pintype "tri_state"))
    )
    (net (code "119") (name "unconnected-(IC6-QH*-Pad9)") (class "Default")
      (node (ref "IC6") (pin "9") (pinfunction "QH*_9") (pintype "tri_state"))
    )
    (net (code "120") (name "unconnected-(IC7-QH*-Pad9)") (class "Default")
      (node (ref "IC7") (pin "9") (pinfunction "QH*_9") (pintype "tri_state"))
    )
    (net (code "121") (name "unconnected-(RESET-P1-Pad4)") (class "Default")
      (node (ref "RESET") (pin "4") (pinfunction "P1_4") (pintype "passive"))
    )
    (net (code "122") (name "unconnected-(RESET-S1-Pad2)") (class "Default")
      (node (ref "RESET") (pin "2") (pinfunction "S1_2") (pintype "passive"))
    )
  )
)
